# module_nRF24.net
KiCad netlist of a schematic drawn in EAGLE
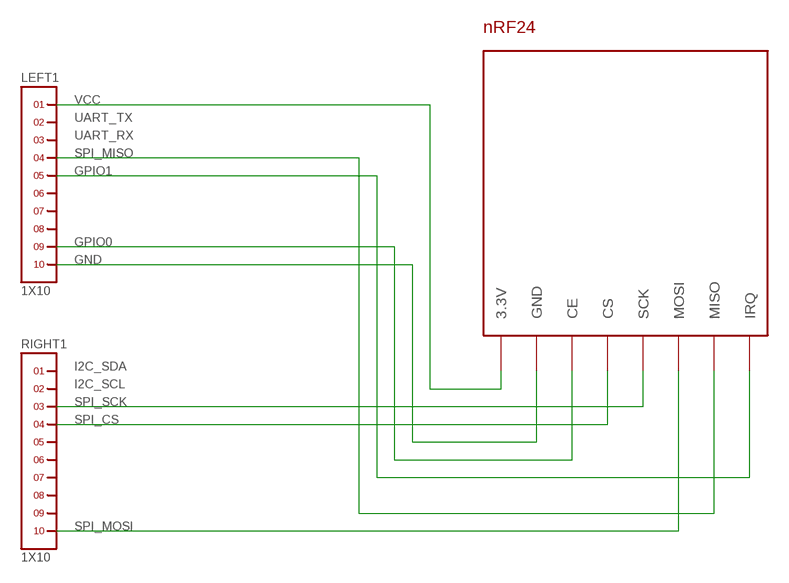
[diagram p0: schematic, sheet 1]

(export (version "E")
  (design (tool "Eeschema 10.0.6"))
  (components
    (comp (ref "LEFT1")
      (value "1X10")
      (footprint "eagle-import:1X10")
      (libsource (lib "eagle-import") (part "1X10"))
    )
    (comp (ref "RIGHT1")
      (value "1X10")
      (footprint "eagle-import:1X10")
      (libsource (lib "eagle-import") (part "1X10"))
    )
    (comp (ref "U$1")
      (value "NRF24")
      (footprint "eagle-import:NRF24")
      (libsource (lib "eagle-import") (part "NRF24"))
    )
  )
  (nets
    (net (code "1") (name "Net-(LEFT1-Pad1)") (class "Default")
      (node (ref "LEFT1") (pin "1") (pinfunction "1_1") (pintype "bidirectional"))
      (node (ref "U$1") (pin "3.3V") (pinfunction "3.3V_3.3V") (pintype "bidirectional"))
    )
    (net (code "2") (name "Net-(LEFT1-Pad4)") (class "Default")
      (node (ref "LEFT1") (pin "4") (pinfunction "4_4") (pintype "bidirectional"))
      (node (ref "U$1") (pin "MISO") (pinfunction "MISO_MISO") (pintype "bidirectional"))
    )
    (net (code "3") (name "Net-(LEFT1-Pad5)") (class "Default")
      (node (ref "LEFT1") (pin "5") (pinfunction "5_5") (pintype "bidirectional"))
      (node (ref "U$1") (pin "IRQ") (pinfunction "IRQ_IRQ") (pintype "bidirectional"))
    )
    (net (code "4") (name "Net-(LEFT1-Pad9)") (class "Default")
      (node (ref "LEFT1") (pin "9") (pinfunction "9_9") (pintype "bidirectional"))
      (node (ref "U$1") (pin "CE") (pinfunction "CE_CE") (pintype "bidirectional"))
    )
    (net (code "5") (name "Net-(LEFT1-Pad10)") (class "Default")
      (node (ref "LEFT1") (pin "10") (pinfunction "10_10") (pintype "bidirectional"))
      (node (ref "U$1") (pin "GND") (pinfunction "GND_GND") (pintype "bidirectional"))
    )
    (net (code "6") (name "Net-(RIGHT1-Pad3)") (class "Default")
      (node (ref "RIGHT1") (pin "3") (pinfunction "3_3") (pintype "bidirectional"))
      (node (ref "U$1") (pin "SCK") (pinfunction "SCK_SCK") (pintype "bidirectional"))
    )
    (net (code "7") (name "Net-(RIGHT1-Pad4)") (class "Default")
      (node (ref "RIGHT1") (pin "4") (pinfunction "4_4") (pintype "bidirectional"))
      (node (ref "U$1") (pin "CS") (pinfunction "CS_CS") (pintype "bidirectional"))
    )
    (net (code "8") (name "Net-(RIGHT1-Pad10)") (class "Default")
      (node (ref "RIGHT1") (pin "10") (pinfunction "10_10") (pintype "bidirectional"))
      (node (ref "U$1") (pin "MOSI") (pinfunction "MOSI_MOSI") (pintype "bidirectional"))
    )
    (net (code "9") (name "unconnected-(LEFT1-Pad2)") (class "Default")
      (node (ref "LEFT1") (pin "2") (pinfunction "2_2") (pintype "bidirectional"))
    )
    (net (code "10") (name "unconnected-(LEFT1-Pad3)") (class "Default")
      (node (ref "LEFT1") (pin "3") (pinfunction "3_3") (pintype "bidirectional"))
    )
    (net (code "11") (name "unconnected-(LEFT1-Pad6)") (class "Default")
      (node (ref "LEFT1") (pin "6") (pinfunction "6_6") (pintype "bidirectional"))
    )
    (net (code "12") (name "unconnected-(LEFT1-Pad7)") (class "Default")
      (node (ref "LEFT1") (pin "7") (pinfunction "7_7") (pintype "bidirectional"))
    )
    (net (code "13") (name "unconnected-(LEFT1-Pad8)") (class "Default")
      (node (ref "LEFT1") (pin "8") (pinfunction "8_8") (pintype "bidirectional"))
    )
    (net (code "14") (name "unconnected-(RIGHT1-Pad1)") (class "Default")
      (node (ref "RIGHT1") (pin "1") (pinfunction "1_1") (pintype "bidirectional"))
    )
    (net (code "15") (name "unconnected-(RIGHT1-Pad2)") (class "Default")
      (node (ref "RIGHT1") (pin "2") (pinfunction "2_2") (pintype "bidirectional"))
    )
    (net (code "16") (name "unconnected-(RIGHT1-Pad5)") (class "Default")
      (node (ref "RIGHT1") (pin "5") (pinfunction "5_5") (pintype "bidirectional"))
    )
    (net (code "17") (name "unconnected-(RIGHT1-Pad6)") (class "Default")
      (node (ref "RIGHT1") (pin "6") (pinfunction "6_6") (pintype "bidirectional"))
    )
    (net (code "18") (name "unconnected-(RIGHT1-Pad7)") (class "Default")
      (node (ref "RIGHT1") (pin "7") (pinfunction "7_7") (pintype "bidirectional"))
    )
    (net (code "19") (name "unconnected-(RIGHT1-Pad8)") (class "Default")
      (node (ref "RIGHT1") (pin "8") (pinfunction "8_8") (pintype "bidirectional"))
    )
    (net (code "20") (name "unconnected-(RIGHT1-Pad9)") (class "Default")
      (node (ref "RIGHT1") (pin "9") (pinfunction "9_9") (pintype "bidirectional"))
    )
  )
)
